# CON_PCI_Express_Mini_P1_52PIN.net
KiCad netlist of a schematic drawn in Altium Designer
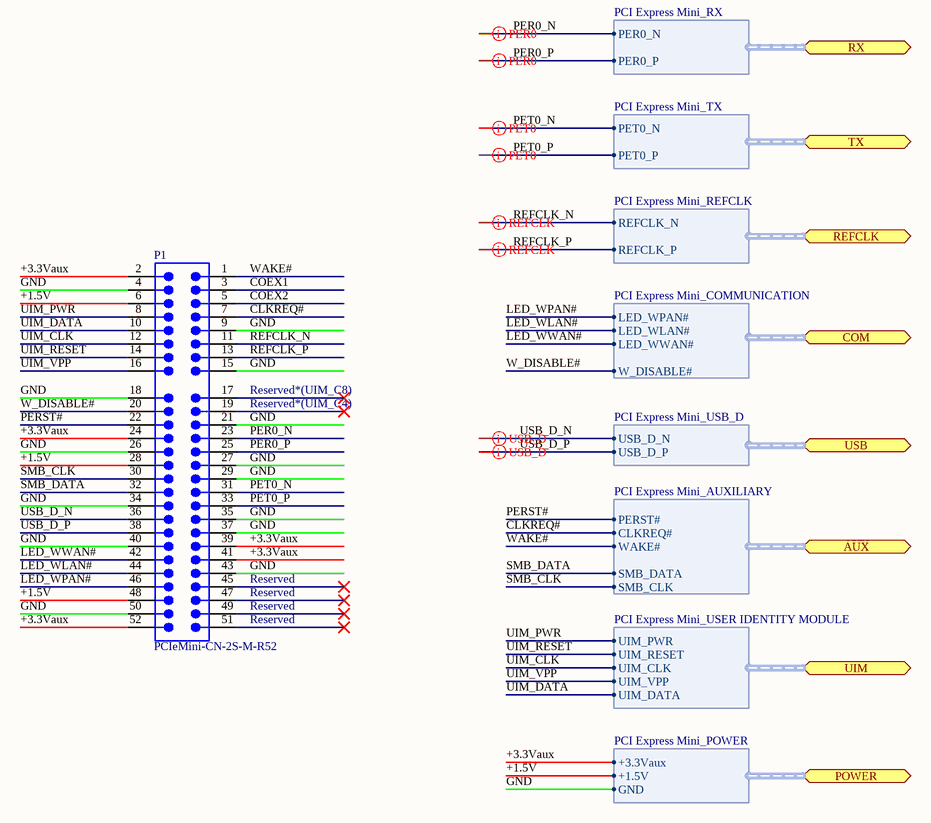
[diagram p0: CON_PCI Express Mini_P1_52PIN.SchDoc]

(export (version "E")
  (design (tool "Eeschema 10.0.6"))
  (components
    (comp (ref "P1")
      (value "PCIeMini-CN-2S-M-R52")
      (footprint "PCIeMini-GF-2D-800-1K-S52")
      (description "Golden finger, PCIeMini, Dual, Staggered, Pitch 0.8mm, 52-Position")
      (fields (field (name "PUBLISHER") "Altium"))
      (libsource (lib "Altium Shanghai") (part "PCIeMini-CN-2S-M-R52"))
    )
  )
  (nets
    (net (code "13") (name "/+1.5V") (class "Default")
      (node (ref "P1") (pin "28") (pinfunction "28_28") (pintype "passive"))
      (node (ref "P1") (pin "48") (pinfunction "48_48") (pintype "passive"))
      (node (ref "P1") (pin "6") (pinfunction "6_6") (pintype "passive"))
    )
    (net (code "14") (name "/+3.3Vaux") (class "Default")
      (node (ref "P1") (pin "2") (pinfunction "2_2") (pintype "passive"))
      (node (ref "P1") (pin "24") (pinfunction "24_24") (pintype "passive"))
      (node (ref "P1") (pin "39") (pinfunction "39_39") (pintype "passive"))
      (node (ref "P1") (pin "41") (pinfunction "41_41") (pintype "passive"))
      (node (ref "P1") (pin "52") (pinfunction "52_52") (pintype "passive"))
    )
    (net (code "15") (name "/CLKREQ#") (class "Default")
      (node (ref "P1") (pin "7") (pinfunction "7_7") (pintype "passive"))
    )
    (net (code "16") (name "/COEX1") (class "Default")
      (node (ref "P1") (pin "3") (pinfunction "3_3") (pintype "passive"))
    )
    (net (code "17") (name "/COEX2") (class "Default")
      (node (ref "P1") (pin "5") (pinfunction "5_5") (pintype "passive"))
    )
    (net (code "18") (name "/GND") (class "Default")
      (node (ref "P1") (pin "15") (pinfunction "15_15") (pintype "passive"))
      (node (ref "P1") (pin "18") (pinfunction "18_18") (pintype "passive"))
      (node (ref "P1") (pin "21") (pinfunction "21_21") (pintype "passive"))
      (node (ref "P1") (pin "26") (pinfunction "26_26") (pintype "passive"))
      (node (ref "P1") (pin "27") (pinfunction "27_27") (pintype "passive"))
      (node (ref "P1") (pin "29") (pinfunction "29_29") (pintype "passive"))
      (node (ref "P1") (pin "34") (pinfunction "34_34") (pintype "passive"))
      (node (ref "P1") (pin "35") (pinfunction "35_35") (pintype "passive"))
      (node (ref "P1") (pin "37") (pinfunction "37_37") (pintype "passive"))
      (node (ref "P1") (pin "4") (pinfunction "4_4") (pintype "passive"))
      (node (ref "P1") (pin "40") (pinfunction "40_40") (pintype "passive"))
      (node (ref "P1") (pin "43") (pinfunction "43_43") (pintype "passive"))
      (node (ref "P1") (pin "50") (pinfunction "50_50") (pintype "passive"))
      (node (ref "P1") (pin "9") (pinfunction "9_9") (pintype "passive"))
    )
    (net (code "19") (name "/LED_WLAN#") (class "Default")
      (node (ref "P1") (pin "44") (pinfunction "44_44") (pintype "passive"))
    )
    (net (code "20") (name "/LED_WPAN#") (class "Default")
      (node (ref "P1") (pin "46") (pinfunction "46_46") (pintype "passive"))
    )
    (net (code "21") (name "/LED_WWAN#") (class "Default")
      (node (ref "P1") (pin "42") (pinfunction "42_42") (pintype "passive"))
    )
    (net (code "22") (name "/PER0_N") (class "Default")
      (node (ref "P1") (pin "23") (pinfunction "23_23") (pintype "passive"))
    )
    (net (code "23") (name "/PER0_P") (class "Default")
      (node (ref "P1") (pin "25") (pinfunction "25_25") (pintype "passive"))
    )
    (net (code "24") (name "/PERST#") (class "Default")
      (node (ref "P1") (pin "22") (pinfunction "22_22") (pintype "passive"))
    )
    (net (code "25") (name "/PET0_N") (class "Default")
      (node (ref "P1") (pin "31") (pinfunction "31_31") (pintype "passive"))
    )
    (net (code "26") (name "/PET0_P") (class "Default")
      (node (ref "P1") (pin "33") (pinfunction "33_33") (pintype "passive"))
    )
    (net (code "27") (name "/REFCLK_N") (class "Default")
      (node (ref "P1") (pin "11") (pinfunction "11_11") (pintype "passive"))
    )
    (net (code "28") (name "/REFCLK_P") (class "Default")
      (node (ref "P1") (pin "13") (pinfunction "13_13") (pintype "passive"))
    )
    (net (code "29") (name "/SMB_CLK") (class "Default")
      (node (ref "P1") (pin "30") (pinfunction "30_30") (pintype "passive"))
    )
    (net (code "30") (name "/SMB_DATA") (class "Default")
      (node (ref "P1") (pin "32") (pinfunction "32_32") (pintype "passive"))
    )
    (net (code "31") (name "/UIM_CLK") (class "Default")
      (node (ref "P1") (pin "12") (pinfunction "12_12") (pintype "passive"))
    )
    (net (code "32") (name "/UIM_DATA") (class "Default")
      (node (ref "P1") (pin "10") (pinfunction "10_10") (pintype "passive"))
    )
    (net (code "33") (name "/UIM_PWR") (class "Default")
      (node (ref "P1") (pin "8") (pinfunction "8_8") (pintype "passive"))
    )
    (net (code "34") (name "/UIM_RESET") (class "Default")
      (node (ref "P1") (pin "14") (pinfunction "14_14") (pintype "passive"))
    )
    (net (code "35") (name "/UIM_VPP") (class "Default")
      (node (ref "P1") (pin "16") (pinfunction "16_16") (pintype "passive"))
    )
    (net (code "36") (name "/USB_D_N") (class "Default")
      (node (ref "P1") (pin "36") (pinfunction "36_36") (pintype "passive"))
    )
    (net (code "37") (name "/USB_D_P") (class "Default")
      (node (ref "P1") (pin "38") (pinfunction "38_38") (pintype "passive"))
    )
    (net (code "38") (name "/WAKE#") (class "Default")
      (node (ref "P1") (pin "1") (pinfunction "1_1") (pintype "passive"))
    )
    (net (code "39") (name "/W_DISABLE#") (class "Default")
      (node (ref "P1") (pin "20") (pinfunction "20_20") (pintype "passive"))
    )
    (net (code "48") (name "unconnected-(P1-Pad17)") (class "Default")
      (node (ref "P1") (pin "17") (pinfunction "17_17") (pintype "passive+no_connect"))
    )
    (net (code "49") (name "unconnected-(P1-Pad19)") (class "Default")
      (node (ref "P1") (pin "19") (pinfunction "19_19") (pintype "passive+no_connect"))
    )
    (net (code "50") (name "unconnected-(P1-Pad45)") (class "Default")
      (node (ref "P1") (pin "45") (pinfunction "45_45") (pintype "passive+no_connect"))
    )
    (net (code "51") (name "unconnected-(P1-Pad47)") (class "Default")
      (node (ref "P1") (pin "47") (pinfunction "47_47") (pintype "passive+no_connect"))
    )
    (net (code "52") (name "unconnected-(P1-Pad49)") (class "Default")
      (node (ref "P1") (pin "49") (pinfunction "49_49") (pintype "passive+no_connect"))
    )
    (net (code "53") (name "unconnected-(P1-Pad51)") (class "Default")
      (node (ref "P1") (pin "51") (pinfunction "51_51") (pintype "passive+no_connect"))
    )
  )
)
